# E-P-010-R1_0_SensorsPowerboard.net
KiCad netlist of a schematic drawn in EAGLE
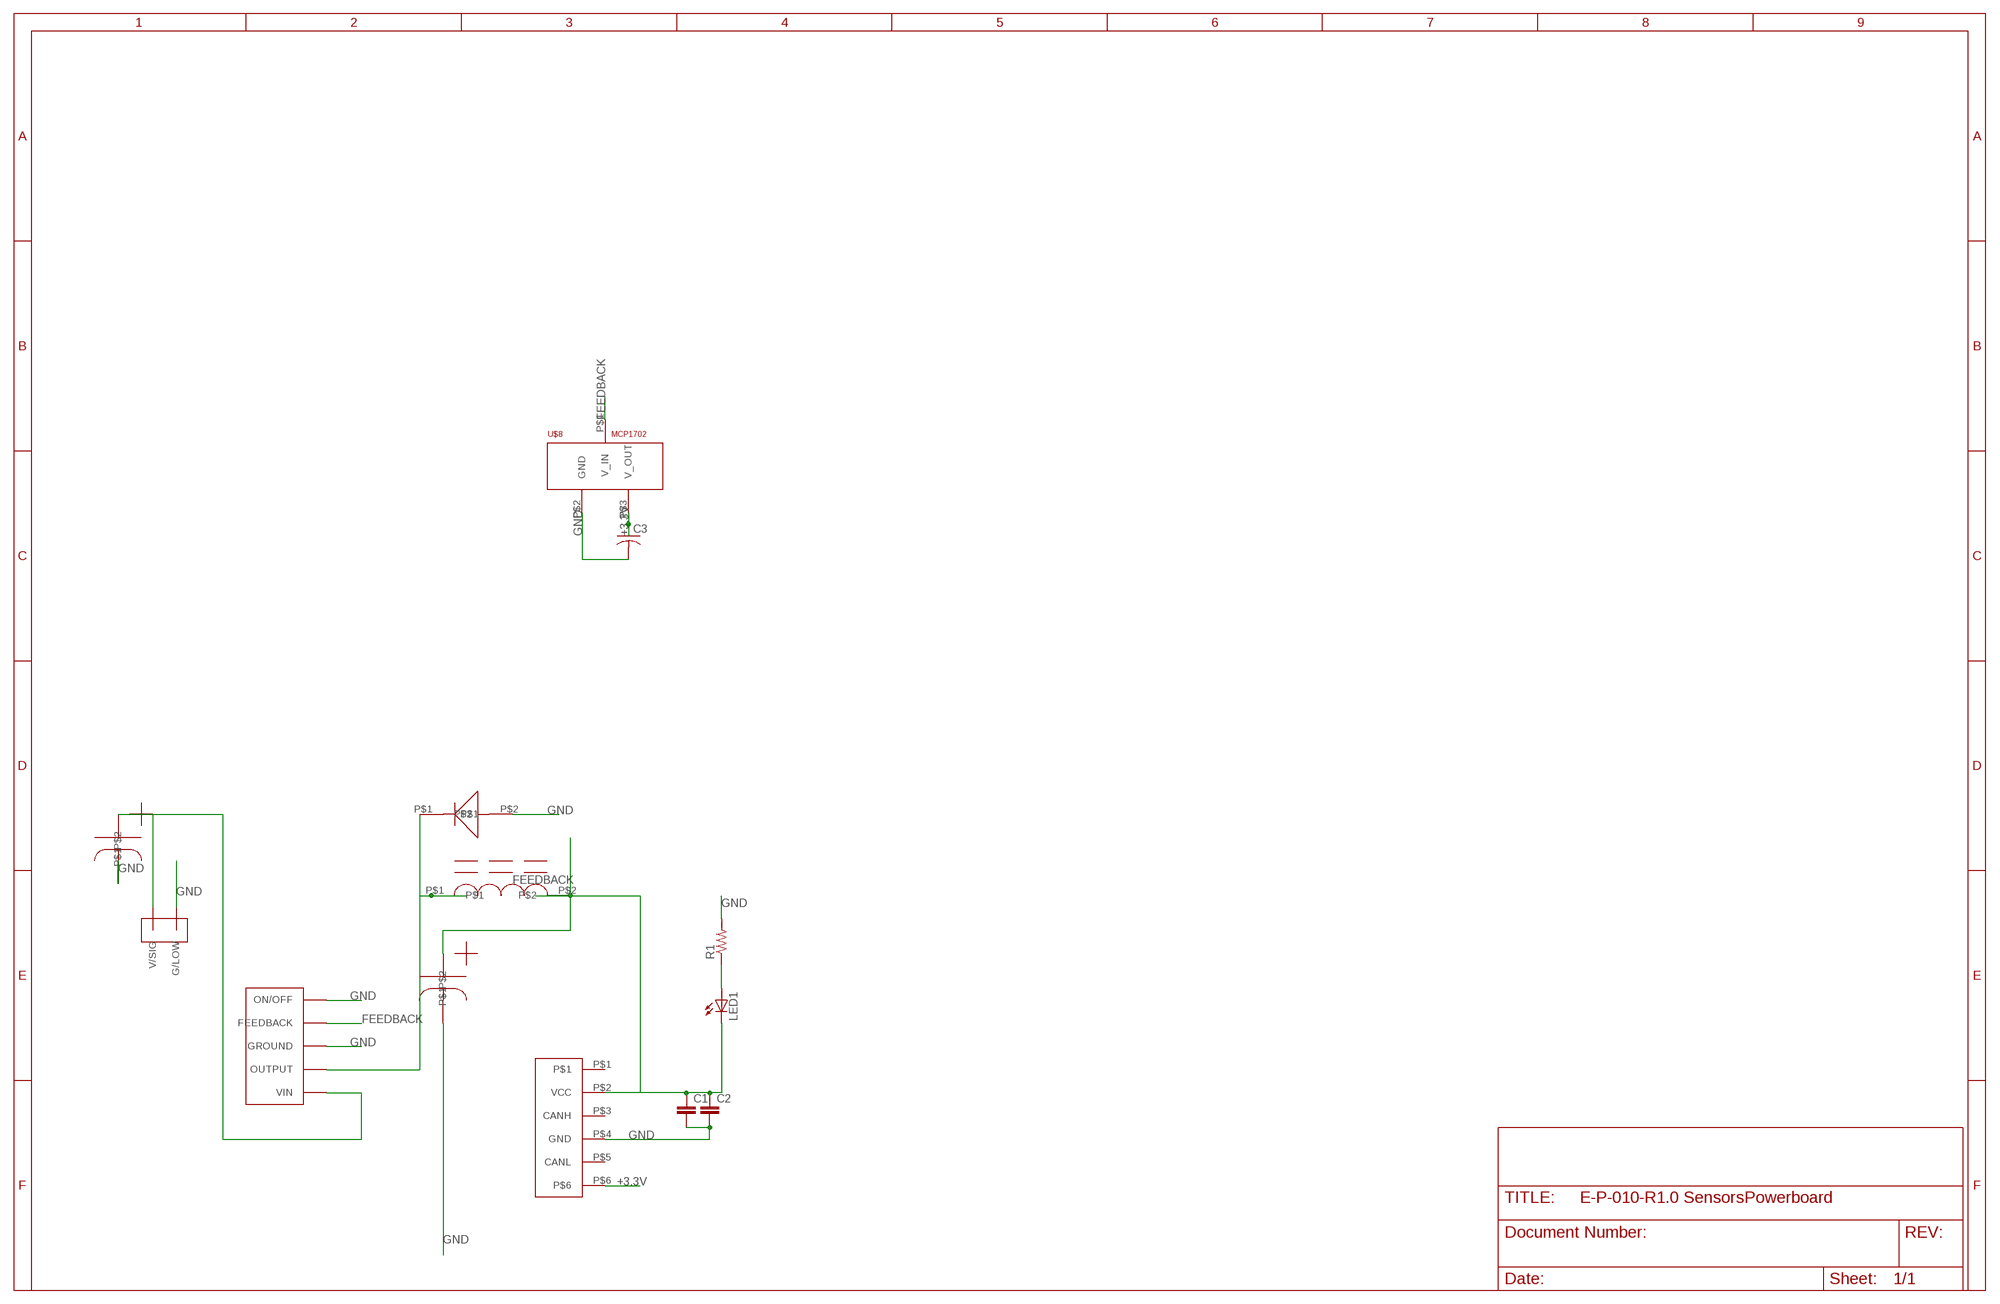
[diagram p0: schematic, sheet 1]

(export (version "E")
  (design (tool "Eeschema 10.0.6"))
  (components
    (comp (ref "C1")
      (value "CAP0805")
      (footprint "eagle-import:0805")
      (libsource (lib "eagle-import") (part "CAP0805"))
    )
    (comp (ref "C2")
      (value "CAP0805")
      (footprint "eagle-import:0805")
      (libsource (lib "eagle-import") (part "CAP0805"))
    )
    (comp (ref "C3")
      (value "C-USC0805")
      (footprint "eagle-import:C0805")
      (libsource (lib "eagle-import") (part "C-USC0805"))
    )
    (comp (ref "LED1")
      (value "LEDSMT1206")
      (footprint "eagle-import:1206")
      (libsource (lib "eagle-import") (part "LEDSMT1206"))
    )
    (comp (ref "R1")
      (value "RESISTOR0805-RES")
      (footprint "eagle-import:0805")
      (libsource (lib "eagle-import") (part "RESISTOR0805-RES"))
    )
    (comp (ref "U$1")
      (value "LM2576")
      (footprint "eagle-import:D2PAK-5")
      (libsource (lib "eagle-import") (part "LM2576"))
    )
    (comp (ref "U$2")
      (value "MBR360GOS")
      (footprint "eagle-import:MBR360GOS")
      (libsource (lib "eagle-import") (part "MBR360GOS"))
    )
    (comp (ref "U$3")
      (value "TE770966")
      (footprint "eagle-import:2X1-MATE-N-LOCK")
      (libsource (lib "eagle-import") (part "TE770966"))
    )
    (comp (ref "U$4")
      (value "CAN_6P6C")
      (footprint "eagle-import:CAN_6P6C")
      (libsource (lib "eagle-import") (part "CAN_6P6C"))
    )
    (comp (ref "U$5")
      (value "CAPESK107M025AC3AA")
      (footprint "eagle-import:ESK107M025AC3AA")
      (libsource (lib "eagle-import") (part "CAPESK107M025AC3AA"))
    )
    (comp (ref "U$6")
      (value "CAPESK108M025AH4EA")
      (footprint "eagle-import:ESK108M025AH4EA")
      (libsource (lib "eagle-import") (part "CAPESK108M025AH4EA"))
    )
    (comp (ref "U$7")
      (value "M1418-ND")
      (footprint "eagle-import:M1418-ND")
      (libsource (lib "eagle-import") (part "M1418-ND"))
    )
    (comp (ref "U$8")
      (value "MCP1702")
      (footprint "eagle-import:SOT-23A")
      (libsource (lib "eagle-import") (part "MCP1702"))
    )
  )
  (nets
    (net (code "1") (name "/+3.3V") (class "Default")
      (node (ref "C3") (pin "1") (pinfunction "1_1") (pintype "passive"))
      (node (ref "U$4") (pin "P$6") (pinfunction "P$6_P$6") (pintype "bidirectional"))
      (node (ref "U$8") (pin "P$3") (pinfunction "V_OUT_P$3") (pintype "bidirectional"))
    )
    (net (code "2") (name "/FEEDBACK") (class "Default")
      (node (ref "C1") (pin "1") (pinfunction "1_1") (pintype "passive"))
      (node (ref "C2") (pin "1") (pinfunction "1_1") (pintype "passive"))
      (node (ref "LED1") (pin "C") (pinfunction "C_C") (pintype "passive"))
      (node (ref "U$1") (pin "4") (pinfunction "FEEDBACK_4") (pintype "bidirectional"))
      (node (ref "U$4") (pin "P$2") (pinfunction "VCC_P$2") (pintype "bidirectional"))
      (node (ref "U$6") (pin "P$1") (pinfunction "P$1_P$1") (pintype "bidirectional"))
      (node (ref "U$7") (pin "P$2") (pinfunction "P$2_P$2") (pintype "bidirectional"))
      (node (ref "U$8") (pin "P$1") (pinfunction "V_IN_P$1") (pintype "bidirectional"))
    )
    (net (code "3") (name "/GND") (class "Default")
      (node (ref "C1") (pin "2") (pinfunction "2_2") (pintype "passive"))
      (node (ref "C2") (pin "2") (pinfunction "2_2") (pintype "passive"))
      (node (ref "C3") (pin "2") (pinfunction "2_2") (pintype "passive"))
      (node (ref "R1") (pin "2") (pinfunction "2_2") (pintype "passive"))
      (node (ref "U$1") (pin "3") (pinfunction "GROUND_3") (pintype "bidirectional"))
      (node (ref "U$1") (pin "5") (pinfunction "ON/OFF_5") (pintype "bidirectional"))
      (node (ref "U$1") (pin "GROUND") (pinfunction "GROUND_GROUND") (pintype "bidirectional"))
      (node (ref "U$2") (pin "P$2") (pinfunction "P$1_P$2") (pintype "bidirectional"))
      (node (ref "U$3") (pin "CIRCUIT2") (pinfunction "G/LOW_CIRCUIT2") (pintype "bidirectional"))
      (node (ref "U$4") (pin "P$4") (pinfunction "GND_P$4") (pintype "bidirectional"))
      (node (ref "U$5") (pin "P$2") (pinfunction "P$2_P$2") (pintype "bidirectional"))
      (node (ref "U$6") (pin "P$2") (pinfunction "P$2_P$2") (pintype "bidirectional"))
      (node (ref "U$8") (pin "P$2") (pinfunction "GND_P$2") (pintype "bidirectional"))
    )
    (net (code "4") (name "Net-(LED1-PadA)") (class "Default")
      (node (ref "LED1") (pin "A") (pinfunction "A_A") (pintype "passive"))
      (node (ref "R1") (pin "1") (pinfunction "1_1") (pintype "passive"))
    )
    (net (code "5") (name "Net-(U$1-OUTPUT)") (class "Default")
      (node (ref "U$1") (pin "2") (pinfunction "OUTPUT_2") (pintype "bidirectional"))
      (node (ref "U$2") (pin "P$1") (pinfunction "P$2_P$1") (pintype "bidirectional"))
      (node (ref "U$7") (pin "P$1") (pinfunction "P$1_P$1") (pintype "bidirectional"))
    )
    (net (code "6") (name "Net-(U$1-VIN)") (class "Default")
      (node (ref "U$1") (pin "1") (pinfunction "VIN_1") (pintype "bidirectional"))
      (node (ref "U$3") (pin "CIRCUIT1") (pinfunction "V/SIG_CIRCUIT1") (pintype "bidirectional"))
      (node (ref "U$5") (pin "P$1") (pinfunction "P$1_P$1") (pintype "bidirectional"))
    )
    (net (code "7") (name "unconnected-(U$4-CANH-PadP$3)") (class "Default")
      (node (ref "U$4") (pin "P$3") (pinfunction "CANH_P$3") (pintype "bidirectional"))
    )
    (net (code "8") (name "unconnected-(U$4-CANL-PadP$5)") (class "Default")
      (node (ref "U$4") (pin "P$5") (pinfunction "CANL_P$5") (pintype "bidirectional"))
    )
    (net (code "9") (name "unconnected-(U$4-PadP$1)") (class "Default")
      (node (ref "U$4") (pin "P$1") (pinfunction "P$1_P$1") (pintype "bidirectional"))
    )
  )
)
